# UART_Translator.net
KiCad netlist of a schematic drawn in Altium Designer
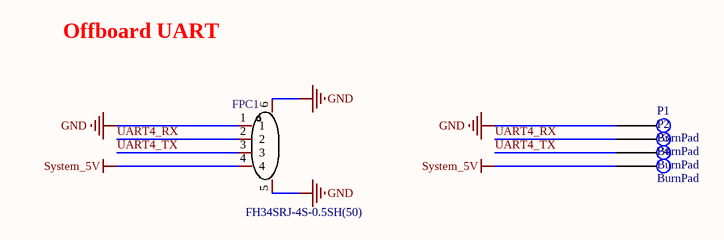
[diagram p0: UART_Translator.SchDoc]

(export (version "E")
  (design (tool "Eeschema 10.0.6"))
  (components
    (comp (ref "FPC1")
      (value "FH34SRJ-4S-0.5SH(50)")
      (footprint "FFC-SMD_4P-P0.50_FH34SRJ-4S-0.5SH")
      (fields (field (name "MANUFACTURER") "HRS(广濑)"))
      (libsource (lib "FPC") (part "FH34SRJ-4S-0.5SH(50)"))
    )
    (comp (ref "P1") (value "BurnPad") (footprint "BurnPad_0.5mm") (libsource (lib "Pad") (part "BurnPad")))
    (comp (ref "P2") (value "BurnPad") (footprint "BurnPad_0.5mm") (libsource (lib "Pad") (part "BurnPad")))
    (comp (ref "P3") (value "BurnPad") (footprint "BurnPad_0.5mm") (libsource (lib "Pad") (part "BurnPad")))
    (comp (ref "P4") (value "BurnPad") (footprint "BurnPad_0.5mm") (libsource (lib "Pad") (part "BurnPad")))
  )
  (nets
    (net (code "1") (name "/UART4_RX") (class "Default")
      (node (ref "FPC1") (pin "2") (pinfunction "2_2") (pintype "passive"))
      (node (ref "P2") (pin "1") (pinfunction "1_1") (pintype "passive"))
    )
    (net (code "2") (name "/UART4_TX") (class "Default")
      (node (ref "FPC1") (pin "3") (pinfunction "3_3") (pintype "passive"))
      (node (ref "P3") (pin "1") (pinfunction "1_1") (pintype "passive"))
    )
    (net (code "3") (name "GND") (class "Default")
      (node (ref "FPC1") (pin "1") (pinfunction "1_1") (pintype "passive"))
      (node (ref "FPC1") (pin "5") (pinfunction "5_5") (pintype "passive"))
      (node (ref "FPC1") (pin "6") (pinfunction "6_6") (pintype "passive"))
      (node (ref "P1") (pin "1") (pinfunction "1_1") (pintype "passive"))
    )
    (net (code "4") (name "System_5V") (class "Default")
      (node (ref "FPC1") (pin "4") (pinfunction "4_4") (pintype "passive"))
      (node (ref "P4") (pin "1") (pinfunction "1_1") (pintype "passive"))
    )
  )
)
